# Alimentation.net
KiCad netlist of a schematic drawn in Altium Designer
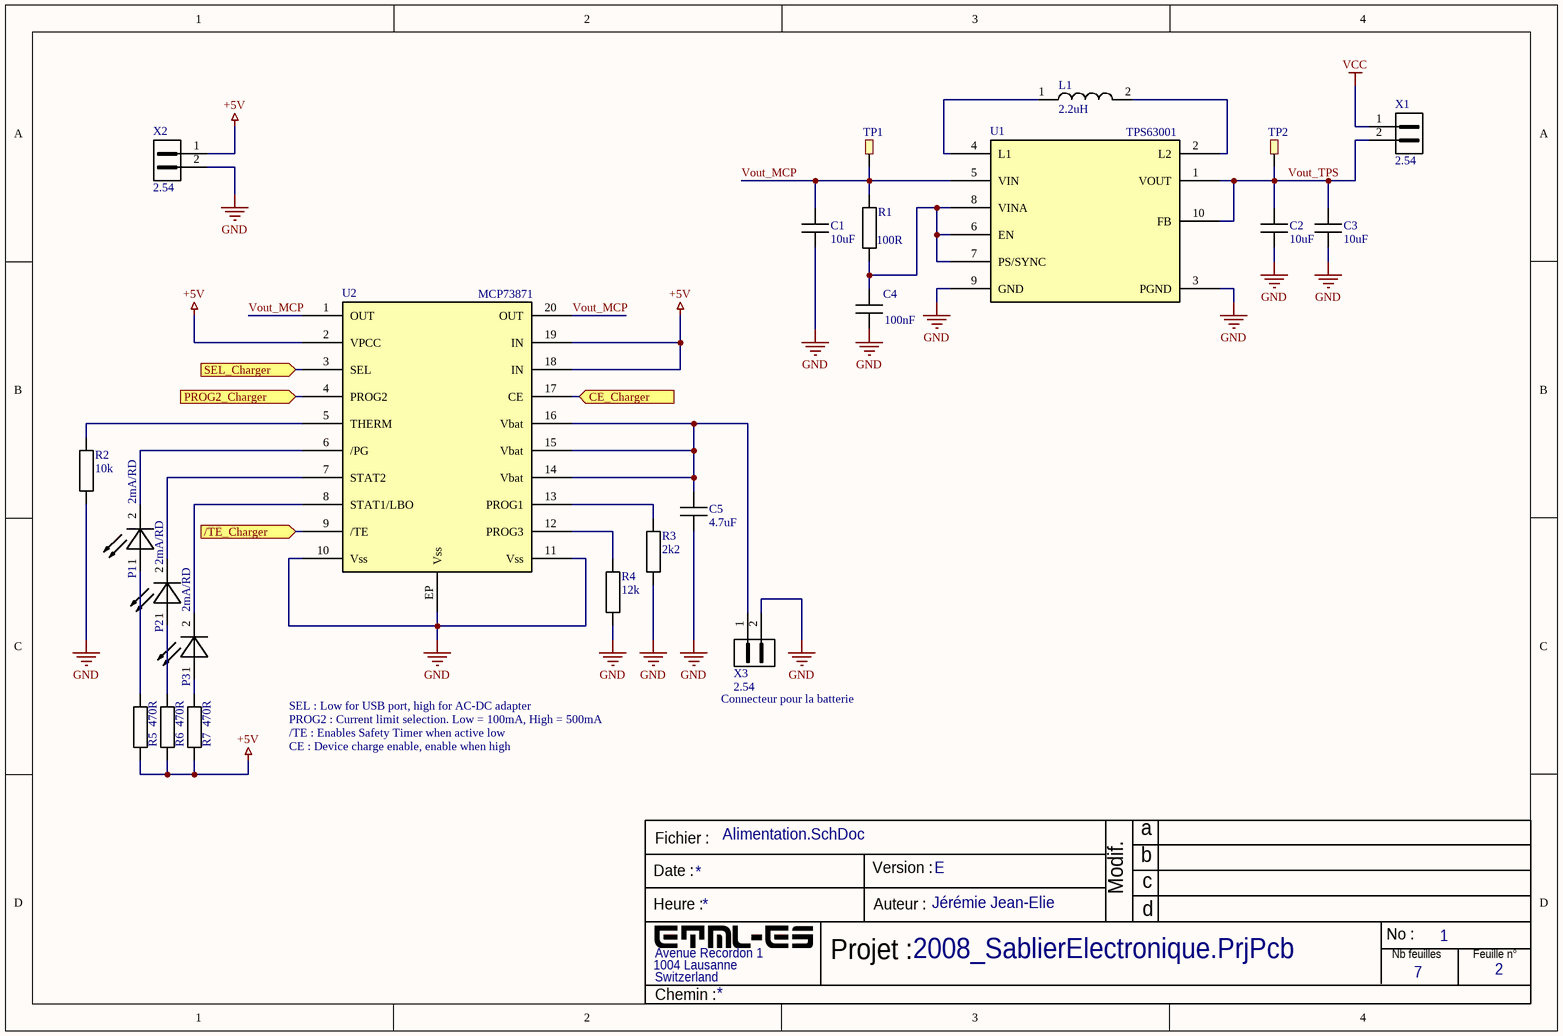
[diagram p0: Alimentation.SchDoc]

(export (version "E")
  (design (tool "Eeschema 10.0.6"))
  (components
    (comp (ref "C1")
      (value "10uF")
      (footprint "CAPC1608X08M")
      (description "CAPC 10uF X5R 10V 20% 1608 (0603 INCH)")
      (fields (field (name "TOLERANCE") "±20%") (field (name "MANUFACTURER") "TDK"))
      (libsource (lib "ETML-ES") (part "CAP"))
    )
    (comp (ref "C2")
      (value "10uF")
      (footprint "CAPC1608X08M")
      (description "CAPC 10uF X5R 10V 20% 1608 (0603 INCH)")
      (fields (field (name "TOLERANCE") "±20%") (field (name "MANUFACTURER") "TDK"))
      (libsource (lib "ETML-ES") (part "CAP"))
    )
    (comp (ref "C3")
      (value "10uF")
      (footprint "CAPC1608X08M")
      (description "CAPC 10uF X5R 10V 20% 1608 (0603 INCH)")
      (fields (field (name "TOLERANCE") "±20%") (field (name "MANUFACTURER") "TDK"))
      (libsource (lib "ETML-ES") (part "CAP"))
    )
    (comp (ref "C4")
      (value "100nF")
      (footprint "CAPC1608X08M")
      (description "CAPC 100nF X7R 50V 10% 1608 (0603 INCH)")
      (fields (field (name "VOLTAGE") "50V") (field (name "MANUFACTURER") "TDK"))
      (libsource (lib "ETML-ES") (part "CAP"))
    )
    (comp (ref "C5")
      (value "4.7uF")
      (footprint "CAPC1608X08M")
      (description "CAPC 4.7uF X5R 16V 10% 1608 (0603 INCH)")
      (fields (field (name "VOLTAGE") "16V") (field (name "TOLERANCE") "±10%"))
      (libsource (lib "ETML-ES") (part "CAP"))
    )
    (comp (ref "L1") (value "2.2uH") (footprint "IND_2.2uH") (libsource (lib "Schlib1") (part "2.2uH")))
    (comp (ref "P1")
      (value "2mA/RD")
      (footprint "LED-PLCC2")
      (description "LED 2 mA 2.2V 625nm Red PLCC2")
      (fields (field (name "MANUFACTURER") "Vishay") (field (name "VOLTAGE") "2.2V"))
      (libsource (lib "ETML-ES") (part "LED"))
    )
    (comp (ref "P2")
      (value "2mA/RD")
      (footprint "LED-PLCC2")
      (description "LED 2 mA 2.2V 625nm Red PLCC2")
      (fields (field (name "MANUFACTURER") "Vishay") (field (name "VOLTAGE") "2.2V"))
      (libsource (lib "ETML-ES") (part "LED"))
    )
    (comp (ref "P3")
      (value "2mA/RD")
      (footprint "LED-PLCC2")
      (description "LED 2 mA 2.2V 625nm Red PLCC2")
      (fields (field (name "MANUFACTURER") "Vishay") (field (name "VOLTAGE") "2.2V"))
      (libsource (lib "ETML-ES") (part "LED"))
    )
    (comp (ref "R1")
      (value "100R")
      (footprint "RESC1608X06M")
      (description "RES 100ohm  ±1% 0.1W  1608 (0603 INCH)")
      (fields (field (name "TOLERANCE") "±1%") (field (name "VOLTAGE") "75V"))
      (libsource (lib "ETML-ES") (part "RES"))
    )
    (comp (ref "R2")
      (value "10k")
      (footprint "RESC1608X06M")
      (description "RES 10kohm  ±1% 0.1W  1608 (0603 INCH)")
      (fields (field (name "TOLERANCE") "±1%") (field (name "VOLTAGE") "75V"))
      (libsource (lib "ETML-ES") (part "RES"))
    )
    (comp (ref "R3")
      (value "2k2")
      (footprint "RESC1608X06M")
      (description "RES 2.2kohm  ±1% 0.1W  1608 (0603 INCH)")
      (fields (field (name "POWER") "0.1W") (field (name "VOLTAGE") "75V"))
      (libsource (lib "ETML-ES") (part "RES"))
    )
    (comp (ref "R4")
      (value "12k")
      (footprint "RESC1608X06M")
      (description "RES 12kohm  ±1% 0.1W  1608 (0603 INCH)")
      (fields (field (name "TOLERANCE") "±1%") (field (name "VOLTAGE") "75V"))
      (libsource (lib "ETML-ES") (part "RES"))
    )
    (comp (ref "R5")
      (value "470R")
      (footprint "RESC1608X06M")
      (description "RES 470ohm  ±1% 0.1W  1608 (0603 INCH)")
      (fields (field (name "VOLTAGE") "75V") (field (name "POWER") "0.1W"))
      (libsource (lib "ETML-ES") (part "RES"))
    )
    (comp (ref "R6")
      (value "470R")
      (footprint "RESC1608X06M")
      (description "RES 470ohm  ±1% 0.1W  1608 (0603 INCH)")
      (fields (field (name "VOLTAGE") "75V") (field (name "POWER") "0.1W"))
      (libsource (lib "ETML-ES") (part "RES"))
    )
    (comp (ref "R7")
      (value "470R")
      (footprint "RESC1608X06M")
      (description "RES 470ohm  ±1% 0.1W  1608 (0603 INCH)")
      (fields (field (name "VOLTAGE") "75V") (field (name "POWER") "0.1W"))
      (libsource (lib "ETML-ES") (part "RES"))
    )
    (comp (ref "TP1")
      (value "TestPoint")
      (footprint "KEYSTONE_5019")
      (libsource (lib "Schlib1") (part "TestPoint"))
    )
    (comp (ref "TP2")
      (value "TestPoint")
      (footprint "KEYSTONE_5019")
      (libsource (lib "Schlib1") (part "TestPoint"))
    )
    (comp (ref "U1") (value "TPS63001") (footprint "DRC0010J") (libsource (lib "Schlib1") (part "TPS63001")))
    (comp (ref "U2")
      (value "MCP73871")
      (footprint "QFN50P400X400X100_HS-21N")
      (libsource (lib "Schlib1") (part "MCP73871"))
    )
    (comp (ref "X1")
      (value "2.54")
      (footprint "PIN-1x02-2.54")
      (description "PIN HEADER 2.54 1x02")
      (fields (field (name "MANUFACTURER") "Würth Electronik") (field (name "VOLTAGE") "250V"))
      (libsource (lib "") (part "CON-PIN-1x02_1"))
    )
    (comp (ref "X2")
      (value "2.54")
      (footprint "PIN-1x02-2.54")
      (description "PIN HEADER 2.54 1x02")
      (fields (field (name "MANUFACTURER") "Würth Electronik") (field (name "VOLTAGE") "250V"))
      (libsource (lib "ETML-ES") (part "CON-PIN-1x02"))
    )
    (comp (ref "X3")
      (value "2.54")
      (footprint "PIN-1x02-2.54")
      (description "PIN HEADER 2.54 1x02")
      (fields (field (name "MANUFACTURER") "Würth Electronik") (field (name "VOLTAGE") "250V"))
      (libsource (lib "") (part "CON-PIN-1x02_2"))
    )
  )
  (nets
    (net (code "1") (name "+5V") (class "Default")
      (node (ref "R5") (pin "1") (pinfunction "1_1") (pintype "passive"))
      (node (ref "R6") (pin "1") (pinfunction "1_1") (pintype "passive"))
      (node (ref "R7") (pin "1") (pinfunction "1_1") (pintype "passive"))
      (node (ref "U2") (pin "18") (pinfunction "IN_18") (pintype "passive"))
      (node (ref "U2") (pin "19") (pinfunction "IN_19") (pintype "passive"))
      (node (ref "U2") (pin "2") (pinfunction "VPCC_2") (pintype "passive"))
      (node (ref "X2") (pin "1") (pinfunction "1_1") (pintype "passive"))
    )
    (net (code "2") (name "/CE_Charger") (class "Default")
      (node (ref "U2") (pin "17") (pinfunction "CE_17") (pintype "passive"))
    )
    (net (code "3") (name "/PROG2_Charger") (class "Default")
      (node (ref "U2") (pin "4") (pinfunction "PROG2_4") (pintype "passive"))
    )
    (net (code "4") (name "/SEL_Charger") (class "Default")
      (node (ref "U2") (pin "3") (pinfunction "SEL_3") (pintype "passive"))
    )
    (net (code "5") (name "/Vout_MCP") (class "Default")
      (node (ref "C1") (pin "2") (pinfunction "2_2") (pintype "passive"))
      (node (ref "R1") (pin "2") (pinfunction "2_2") (pintype "passive"))
      (node (ref "TP1") (pin "1") (pinfunction "1_1") (pintype "passive"))
      (node (ref "U1") (pin "5") (pinfunction "VIN_5") (pintype "passive"))
      (node (ref "U2") (pin "1") (pinfunction "OUT_1") (pintype "passive"))
      (node (ref "U2") (pin "20") (pinfunction "OUT_20") (pintype "passive"))
    )
    (net (code "6") (name "/Vout_TPS") (class "Default")
      (node (ref "C2") (pin "2") (pinfunction "2_2") (pintype "passive"))
      (node (ref "C3") (pin "2") (pinfunction "2_2") (pintype "passive"))
      (node (ref "TP2") (pin "1") (pinfunction "1_1") (pintype "passive"))
      (node (ref "U1") (pin "1") (pinfunction "VOUT_1") (pintype "passive"))
      (node (ref "U1") (pin "10") (pinfunction "FB_10") (pintype "passive"))
      (node (ref "X1") (pin "2") (pinfunction "2_2") (pintype "passive"))
    )
    (net (code "7") (name "/{slash}TE_Charger") (class "Default")
      (node (ref "U2") (pin "9") (pinfunction "/TE_9") (pintype "passive"))
    )
    (net (code "8") (name "GND") (class "Default")
      (node (ref "C1") (pin "1") (pinfunction "1_1") (pintype "passive"))
      (node (ref "C2") (pin "1") (pinfunction "1_1") (pintype "passive"))
      (node (ref "C3") (pin "1") (pinfunction "1_1") (pintype "passive"))
      (node (ref "C4") (pin "1") (pinfunction "1_1") (pintype "passive"))
      (node (ref "C5") (pin "1") (pinfunction "1_1") (pintype "passive"))
      (node (ref "R2") (pin "1") (pinfunction "1_1") (pintype "passive"))
      (node (ref "R3") (pin "1") (pinfunction "1_1") (pintype "passive"))
      (node (ref "R4") (pin "1") (pinfunction "1_1") (pintype "passive"))
      (node (ref "U1") (pin "3") (pinfunction "PGND_3") (pintype "passive"))
      (node (ref "U1") (pin "9") (pinfunction "GND_9") (pintype "passive"))
      (node (ref "U2") (pin "10") (pinfunction "Vss_10") (pintype "passive"))
      (node (ref "U2") (pin "11") (pinfunction "Vss_11") (pintype "passive"))
      (node (ref "U2") (pin "EP") (pinfunction "Vss_EP") (pintype "passive"))
      (node (ref "X2") (pin "2") (pinfunction "2_2") (pintype "passive"))
      (node (ref "X3") (pin "2") (pinfunction "2_2") (pintype "passive"))
    )
    (net (code "9") (name "Net-(C5-Pad2)") (class "Default")
      (node (ref "C5") (pin "2") (pinfunction "2_2") (pintype "passive"))
      (node (ref "U2") (pin "14") (pinfunction "Vbat_14") (pintype "passive"))
      (node (ref "U2") (pin "15") (pinfunction "Vbat_15") (pintype "passive"))
      (node (ref "U2") (pin "16") (pinfunction "Vbat_16") (pintype "passive"))
      (node (ref "X3") (pin "1") (pinfunction "1_1") (pintype "passive"))
    )
    (net (code "10") (name "Net-(P1-A)") (class "Default")
      (node (ref "P1") (pin "1") (pinfunction "A_1") (pintype "passive"))
      (node (ref "R5") (pin "2") (pinfunction "2_2") (pintype "passive"))
    )
    (net (code "11") (name "Net-(P1-K)") (class "Default")
      (node (ref "P1") (pin "2") (pinfunction "K_2") (pintype "passive"))
      (node (ref "U2") (pin "6") (pinfunction "/PG_6") (pintype "passive"))
    )
    (net (code "12") (name "Net-(P2-A)") (class "Default")
      (node (ref "P2") (pin "1") (pinfunction "A_1") (pintype "passive"))
      (node (ref "R6") (pin "2") (pinfunction "2_2") (pintype "passive"))
    )
    (net (code "13") (name "Net-(P2-K)") (class "Default")
      (node (ref "P2") (pin "2") (pinfunction "K_2") (pintype "passive"))
      (node (ref "U2") (pin "7") (pinfunction "STAT2_7") (pintype "passive"))
    )
    (net (code "14") (name "Net-(P3-A)") (class "Default")
      (node (ref "P3") (pin "1") (pinfunction "A_1") (pintype "passive"))
      (node (ref "R7") (pin "2") (pinfunction "2_2") (pintype "passive"))
    )
    (net (code "15") (name "Net-(P3-K)") (class "Default")
      (node (ref "P3") (pin "2") (pinfunction "K_2") (pintype "passive"))
      (node (ref "U2") (pin "8") (pinfunction "STAT1/LBO_8") (pintype "passive"))
    )
    (net (code "16") (name "Net-(U1-EN)") (class "Default")
      (node (ref "C4") (pin "2") (pinfunction "2_2") (pintype "passive"))
      (node (ref "R1") (pin "1") (pinfunction "1_1") (pintype "passive"))
      (node (ref "U1") (pin "6") (pinfunction "EN_6") (pintype "passive"))
      (node (ref "U1") (pin "7") (pinfunction "PS/SYNC_7") (pintype "passive"))
      (node (ref "U1") (pin "8") (pinfunction "VINA_8") (pintype "passive"))
    )
    (net (code "17") (name "Net-(U1-L1)") (class "Default")
      (node (ref "L1") (pin "1") (pintype "passive"))
      (node (ref "U1") (pin "4") (pinfunction "L1_4") (pintype "passive"))
    )
    (net (code "18") (name "Net-(U1-L2)") (class "Default")
      (node (ref "L1") (pin "2") (pintype "passive"))
      (node (ref "U1") (pin "2") (pinfunction "L2_2") (pintype "passive"))
    )
    (net (code "19") (name "Net-(U2-PROG1)") (class "Default")
      (node (ref "R3") (pin "2") (pinfunction "2_2") (pintype "passive"))
      (node (ref "U2") (pin "13") (pinfunction "PROG1_13") (pintype "passive"))
    )
    (net (code "20") (name "Net-(U2-PROG3)") (class "Default")
      (node (ref "R4") (pin "2") (pinfunction "2_2") (pintype "passive"))
      (node (ref "U2") (pin "12") (pinfunction "PROG3_12") (pintype "passive"))
    )
    (net (code "21") (name "Net-(U2-THERM)") (class "Default")
      (node (ref "R2") (pin "2") (pinfunction "2_2") (pintype "passive"))
      (node (ref "U2") (pin "5") (pinfunction "THERM_5") (pintype "passive"))
    )
    (net (code "22") (name "VCC") (class "Default")
      (node (ref "X1") (pin "1") (pinfunction "1_1") (pintype "passive"))
    )
  )
)
